# LOGIC.net
KiCad netlist of a schematic drawn in Altium Designer
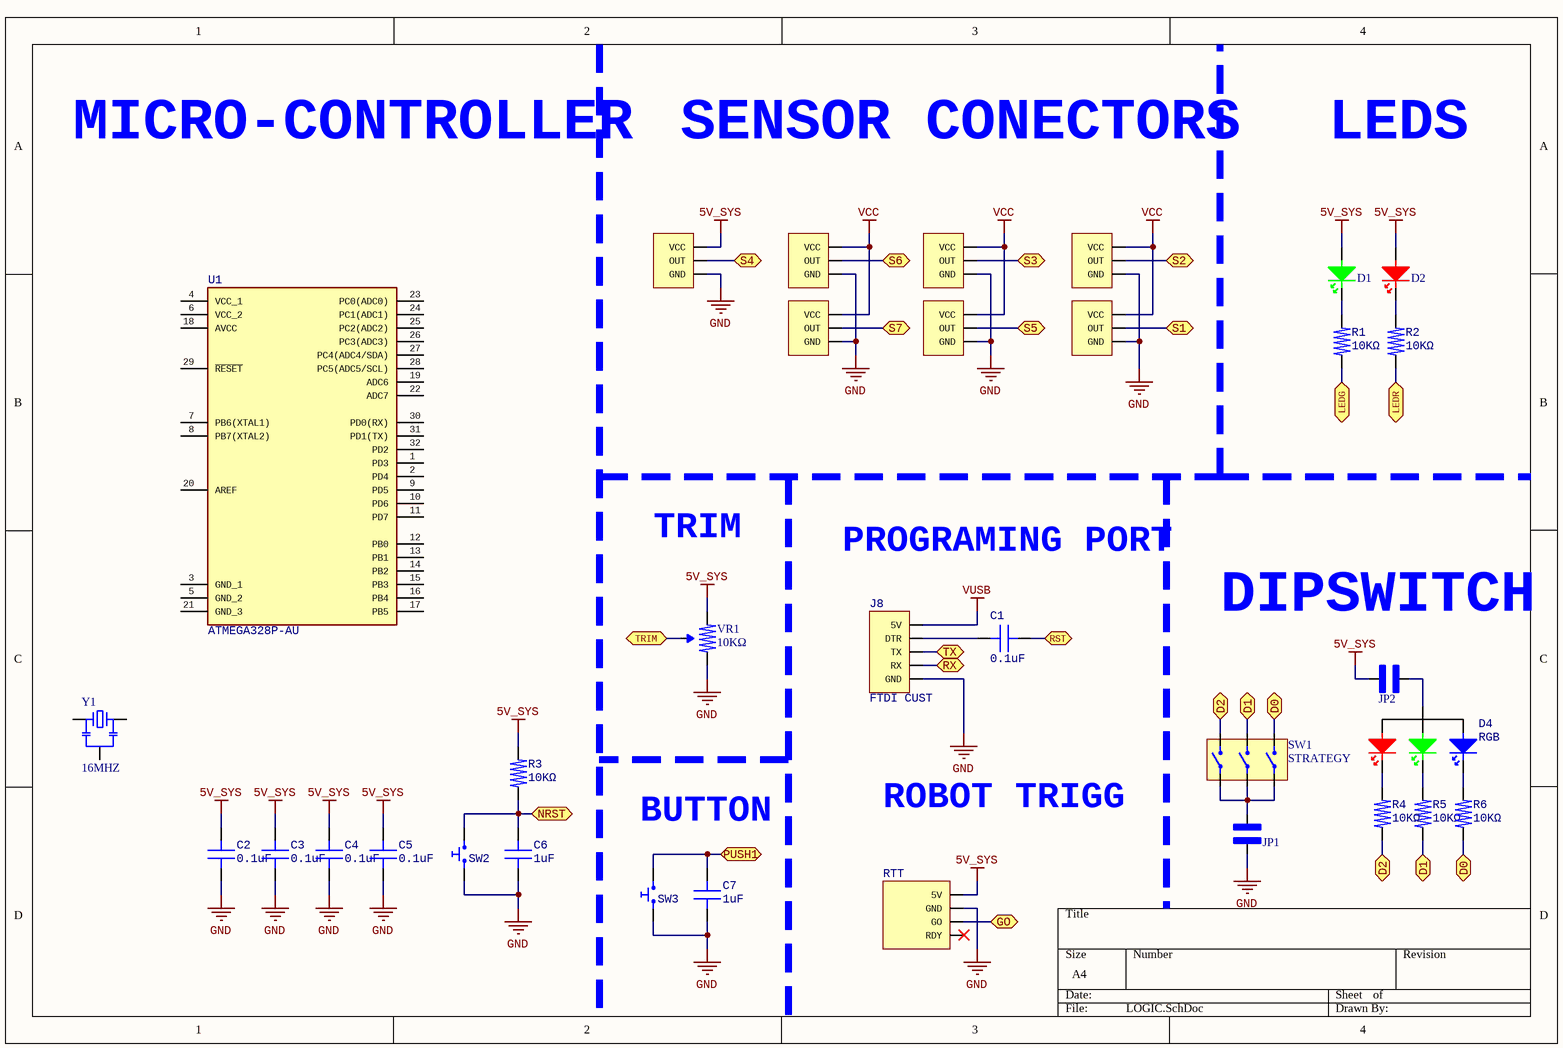
[diagram p0: LOGIC.SchDoc]

(export (version "E")
  (design (tool "Eeschema 10.0.6"))
  (components
    (comp (ref "C1")
      (value "0.1uF")
      (footprint "CAP0603")
      (description "Capacitor, Multilayer, Ceramic, 25V, 10%, X7R, 15% Tc, 0.1Uf, Surface Mount, 0603")
      (fields
        (field (name "MANUFACTURER") "KEMET")
        (field (name "MANUFACTURER PART NUMBER") "C0603C104K3RACTU")
      )
      (libsource (lib "CERAMIC CAPACITORS") (part "C0.1uF 25V X7R"))
    )
    (comp (ref "C2")
      (value "0.1uF")
      (footprint "CAP0603")
      (description "Capacitor, Multilayer, Ceramic, 25V, 10%, X7R, 15% Tc, 0.1Uf, Surface Mount, 0603")
      (fields
        (field (name "MANUFACTURER") "KEMET")
        (field (name "MANUFACTURER PART NUMBER") "C0603C104K3RACTU")
      )
      (libsource (lib "CERAMIC CAPACITORS") (part "C0.1uF 25V X7R"))
    )
    (comp (ref "C3")
      (value "0.1uF")
      (footprint "CAP0603")
      (description "Capacitor, Multilayer, Ceramic, 25V, 10%, X7R, 15% Tc, 0.1Uf, Surface Mount, 0603")
      (fields
        (field (name "MANUFACTURER") "KEMET")
        (field (name "MANUFACTURER PART NUMBER") "C0603C104K3RACTU")
      )
      (libsource (lib "CERAMIC CAPACITORS") (part "C0.1uF 25V X7R"))
    )
    (comp (ref "C4")
      (value "0.1uF")
      (footprint "CAP0603")
      (description "Capacitor, Multilayer, Ceramic, 25V, 10%, X7R, 15% Tc, 0.1Uf, Surface Mount, 0603")
      (fields
        (field (name "MANUFACTURER") "KEMET")
        (field (name "MANUFACTURER PART NUMBER") "C0603C104K3RACTU")
      )
      (libsource (lib "CERAMIC CAPACITORS") (part "C0.1uF 25V X7R"))
    )
    (comp (ref "C5")
      (value "0.1uF")
      (footprint "CAP0603")
      (description "Capacitor, Multilayer, Ceramic, 25V, 10%, X7R, 15% Tc, 0.1Uf, Surface Mount, 0603")
      (fields
        (field (name "MANUFACTURER") "KEMET")
        (field (name "MANUFACTURER PART NUMBER") "C0603C104K3RACTU")
      )
      (libsource (lib "CERAMIC CAPACITORS") (part "C0.1uF 25V X7R"))
    )
    (comp (ref "C6")
      (value "1uF")
      (footprint "CAP0603")
      (description "Multilayer Ceramic Capacitor, 1 uF, 50 V, ï¿½ 10%, X5R, 0603 [1608 Metric]")
      (fields
        (field (name "MANUFACTURER") "TDK")
        (field (name "MANUFACTURER PART NUMBER") "C1608X5R1H105K080AB")
      )
      (libsource (lib "CERAMIC CAPACITORS") (part "C1uF 50V X5R"))
    )
    (comp (ref "C7")
      (value "1uF")
      (footprint "CAP0603")
      (description "Multilayer Ceramic Capacitor, 1 uF, 50 V, ï¿½ 10%, X5R, 0603 [1608 Metric]")
      (fields
        (field (name "MANUFACTURER") "TDK")
        (field (name "MANUFACTURER PART NUMBER") "C1608X5R1H105K080AB")
      )
      (libsource (lib "CERAMIC CAPACITORS") (part "C1uF 50V X5R"))
    )
    (comp (ref "D1")
      (value "G")
      (footprint "LED0603 GREEN")
      (description "WURTH ELEKTRONIK - 150060VS75000 - LED, Green, SMD, 0603, 30 mA, 2 V, 570 nm")
      (fields
        (field (name "MANUFACTURER") "Wurth Electronics")
        (field (name "MANUFACTURER PART NUMBER") "150060VS75000")
      )
      (libsource (lib "LEDS") (part "GREEN LED 0603"))
    )
    (comp (ref "D2")
      (value "R")
      (footprint "LED0603 RED")
      (description "Led, Red, 630 Nm, 1.9 V, 30 Ma, 60 Mcd Rohs Compliant: Yes ¦Wurth Elektronik 150060SS75000")
      (fields
        (field (name "MANUFACTURER") "Wurth Electronics")
        (field (name "MANUFACTURER PART NUMBER") "150060SS75000")
      )
      (libsource (lib "LEDS") (part "RED LED 0603"))
    )
    (comp (ref "D4")
      (value "RGB")
      (footprint "LED RGB FM-B2020RGBA-HG")
      (description "LED RGB")
      (libsource (lib "LEDS") (part "RGB LED FM-B2020RGBA-HG"))
    )
    (comp (ref "J1")
      (value "GENERIC SENSOR 3X")
      (footprint "PINHEADER SENSOR CONNECTOR 3X")
      (description "PADS PARA CONECTAR UN SENSOR CON 1 LINEA DE VOLTAJE INDEPENDIENTE.")
      (libsource (lib "CONNECTORS") (part "GENERIC SENSOR 3X"))
    )
    (comp (ref "J2")
      (value "GENERIC SENSOR 3X")
      (footprint "PINHEADER SENSOR CONNECTOR 3X")
      (description "PADS PARA CONECTAR UN SENSOR CON 1 LINEA DE VOLTAJE INDEPENDIENTE.")
      (libsource (lib "CONNECTORS") (part "GENERIC SENSOR 3X"))
    )
    (comp (ref "J3")
      (value "GENERIC SENSOR 3X")
      (footprint "PINHEADER SENSOR CONNECTOR 3X")
      (description "PADS PARA CONECTAR UN SENSOR CON 1 LINEA DE VOLTAJE INDEPENDIENTE.")
      (libsource (lib "CONNECTORS") (part "GENERIC SENSOR 3X"))
    )
    (comp (ref "J4")
      (value "GENERIC SENSOR 3X")
      (footprint "PINHEADER SENSOR CONNECTOR 3X")
      (description "PADS PARA CONECTAR UN SENSOR CON 1 LINEA DE VOLTAJE INDEPENDIENTE.")
      (libsource (lib "CONNECTORS") (part "GENERIC SENSOR 3X"))
    )
    (comp (ref "J5")
      (value "GENERIC SENSOR 3X")
      (footprint "PINHEADER SENSOR CONNECTOR 3X")
      (description "PADS PARA CONECTAR UN SENSOR CON 1 LINEA DE VOLTAJE INDEPENDIENTE.")
      (libsource (lib "CONNECTORS") (part "GENERIC SENSOR 3X"))
    )
    (comp (ref "J6")
      (value "GENERIC SENSOR 3X")
      (footprint "PINHEADER SENSOR CONNECTOR 3X")
      (description "PADS PARA CONECTAR UN SENSOR CON 1 LINEA DE VOLTAJE INDEPENDIENTE.")
      (libsource (lib "CONNECTORS") (part "GENERIC SENSOR 3X"))
    )
    (comp (ref "J7")
      (value "GENERIC SENSOR 3X")
      (footprint "PINHEADER SENSOR CONNECTOR 3X")
      (description "PADS PARA CONECTAR UN SENSOR CON 1 LINEA DE VOLTAJE INDEPENDIENTE.")
      (libsource (lib "CONNECTORS") (part "GENERIC SENSOR 3X"))
    )
    (comp (ref "J8")
      (value "FTDI CUST")
      (footprint "UART PROG CONN")
      (description "GENERIC UART PROGRAMING PORT FOR ARDUINO CUSTOM BOARDS")
      (libsource (lib "CONNECTORS") (part "UART PROG"))
    )
    (comp (ref "J9")
      (value "RTT")
      (footprint "ING. MAKER RTT")
      (description "CONECTOR PINHEADER PARA ARRANCADPR ING. MAKER")
      (libsource (lib "CONNECTORS") (part "ING. MAKER RTT"))
    )
    (comp (ref "JP1")
      (value "ENABLE DPSW")
      (footprint "JUMPER 2 PADS")
      (description "JUMPER SMD CON 2 PADS NORMALMENTE ABIERTO")
      (libsource (lib "JUMPERS") (part "SINGLE JUMPER NO"))
    )
    (comp (ref "JP2")
      (value "ENABLE RGB")
      (footprint "JUMPER 2 PADS")
      (description "JUMPER SMD CON 2 PADS NORMALMENTE ABIERTO")
      (libsource (lib "JUMPERS") (part "SINGLE JUMPER NO"))
    )
    (comp (ref "R1")
      (value "10KΩ")
      (footprint "RES0603")
      (description "SMD Chip Resistor, 1 kOhm, ï¿½ 1%, 100 mW, 0603 [1608 Metric], Thick Film, General Purpose")
      (fields
        (field (name "MANUFACTURER") "Yageo")
        (field (name "MANUFACTURER PART NUMBER") "RC0603FR-101KL")
      )
      (libsource (lib "RESISTORS") (part "R1KΩ"))
    )
    (comp (ref "R2")
      (value "10KΩ")
      (footprint "RES0603")
      (description "SMD Chip Resistor, 1 kOhm, ï¿½ 1%, 100 mW, 0603 [1608 Metric], Thick Film, General Purpose")
      (fields
        (field (name "MANUFACTURER") "Yageo")
        (field (name "MANUFACTURER PART NUMBER") "RC0603FR-101KL")
      )
      (libsource (lib "RESISTORS") (part "R1KΩ"))
    )
    (comp (ref "R3")
      (value "10KΩ")
      (footprint "RES0603")
      (description "SMD Chip Resistor, 10 kOhm, ï¿½ 5%, 100 mW, 0603 [1608 Metric], Thick Film, General Purpose")
      (fields
        (field (name "MANUFACTURER") "Yageo")
        (field (name "MANUFACTURER PART NUMBER") "RC0603JR-0710KL")
      )
      (libsource (lib "RESISTORS") (part "R10KΩ"))
    )
    (comp (ref "R4")
      (value "10KΩ")
      (footprint "RES0603")
      (description "SMD Chip Resistor, 1 kOhm, ï¿½ 1%, 100 mW, 0603 [1608 Metric], Thick Film, General Purpose")
      (fields
        (field (name "MANUFACTURER") "Yageo")
        (field (name "MANUFACTURER PART NUMBER") "RC0603FR-101KL")
      )
      (libsource (lib "RESISTORS") (part "R1KΩ"))
    )
    (comp (ref "R5")
      (value "10KΩ")
      (footprint "RES0603")
      (description "SMD Chip Resistor, 1 kOhm, ï¿½ 1%, 100 mW, 0603 [1608 Metric], Thick Film, General Purpose")
      (fields
        (field (name "MANUFACTURER") "Yageo")
        (field (name "MANUFACTURER PART NUMBER") "RC0603FR-101KL")
      )
      (libsource (lib "RESISTORS") (part "R1KΩ"))
    )
    (comp (ref "R6")
      (value "10KΩ")
      (footprint "RES0603")
      (description "SMD Chip Resistor, 1 kOhm, ï¿½ 1%, 100 mW, 0603 [1608 Metric], Thick Film, General Purpose")
      (fields
        (field (name "MANUFACTURER") "Yageo")
        (field (name "MANUFACTURER PART NUMBER") "RC0603FR-101KL")
      )
      (libsource (lib "RESISTORS") (part "R1KΩ"))
    )
    (comp (ref "SW1")
      (value "STRATEGY")
      (footprint "2193MSTR")
      (description "Switch DIP ON OFF SPST 3 Raised Slide 0.1A 20VDC Gull Wing 2000Cycles 2.54mm SMD Tube")
      (fields (field (name "MANUFACTURER") "CTS") (field (name "MANUFACTURER PART NUMBER") "219-3MST"))
      (libsource (lib "DIP SWITCHES") (part "219-3MST"))
    )
    (comp (ref "SW2")
      (value "RESET")
      (footprint "PTS810SJK250SMTRLFS")
      (description "Switch Tactile N.O. SPST Button J-Bend 0.05A 16VDC 50000Cycle 2.55N SMD T/R")
      (fields
        (field (name "MANUFACTURER") "ITT C&K")
        (field (name "MANUFACTURER PART NUMBER") "PTS810SJK250SMTRLFS")
      )
      (libsource (lib "PUSH BUTTONS") (part "PTS810SJK250SMTR LFS"))
    )
    (comp (ref "SW3")
      (value "BUTTON1")
      (footprint "PTS810SJK250SMTRLFS")
      (description "Switch Tactile N.O. SPST Button J-Bend 0.05A 16VDC 50000Cycle 2.55N SMD T/R")
      (fields
        (field (name "MANUFACTURER") "ITT C&K")
        (field (name "MANUFACTURER PART NUMBER") "PTS810SJK250SMTRLFS")
      )
      (libsource (lib "PUSH BUTTONS") (part "PTS810SJK250SMTR LFS"))
    )
    (comp (ref "U1")
      (value "ATMEGA328P-AU")
      (footprint "TQFP-32")
      (description "Risc Microcontroller, 8-BIT, Flash, AVR Risc Cpu, 20MHZ, Cmos, PQFP32")
      (fields (field (name "MANUFACTURER") "Microchip"))
      (libsource (lib "MICRO CONTROLLERS") (part "ATMEGA328P-AU"))
    )
    (comp (ref "VR1")
      (value "10KΩ")
      (footprint "TC33X2503E")
      (description "Cermet trimmer potentiometer, 10 kΩ, 0.1 W, SMD, on top, TC33X-2-103E")
      (fields (field (name "MANUFACTURER") "Bourns") (field (name "MANUFACTURER PART NUMBER") "TC33X-2-103E"))
      (libsource (lib "VARIABLE RESISTORS") (part "10KΩ"))
    )
    (comp (ref "Y1")
      (value "16MHZ")
      (footprint "CSTCE16M0V53R0")
      (libsource (lib "CRYSTAL") (part "RESONATOR 16MHZ CSTCE16M0V53-R0"))
    )
  )
  (nets
    (net (code "1") (name "/D0") (class "Default")
      (node (ref "R6") (pin "1") (pinfunction "K_1") (pintype "passive"))
      (node (ref "SW1") (pin "4") (pinfunction "NO_2_4") (pintype "passive"))
    )
    (net (code "2") (name "/D1") (class "Default")
      (node (ref "R5") (pin "1") (pinfunction "K_1") (pintype "passive"))
      (node (ref "SW1") (pin "5") (pinfunction "NO_2_5") (pintype "passive"))
    )
    (net (code "3") (name "/D2") (class "Default")
      (node (ref "R4") (pin "1") (pinfunction "K_1") (pintype "passive"))
      (node (ref "SW1") (pin "6") (pinfunction "NO_2_6") (pintype "passive"))
    )
    (net (code "4") (name "/GO") (class "Default")
      (node (ref "J9") (pin "3") (pinfunction "GO_3") (pintype "passive"))
    )
    (net (code "5") (name "/LEDG") (class "Default")
      (node (ref "R1") (pin "1") (pinfunction "K_1") (pintype "passive"))
    )
    (net (code "6") (name "/LEDR") (class "Default")
      (node (ref "R2") (pin "1") (pinfunction "K_1") (pintype "passive"))
    )
    (net (code "7") (name "/NRST") (class "Default")
      (node (ref "C6") (pin "2") (pinfunction "A_2") (pintype "passive"))
      (node (ref "R3") (pin "1") (pinfunction "K_1") (pintype "passive"))
      (node (ref "SW2") (pin "2") (pinfunction "NO_2_2") (pintype "passive"))
    )
    (net (code "8") (name "/PUSH1") (class "Default")
      (node (ref "C7") (pin "2") (pinfunction "A_2") (pintype "passive"))
      (node (ref "SW3") (pin "2") (pinfunction "NO_2_2") (pintype "passive"))
    )
    (net (code "9") (name "/RST") (class "Default")
      (node (ref "C1") (pin "1") (pinfunction "K_1") (pintype "passive"))
    )
    (net (code "10") (name "/RX") (class "Default")
      (node (ref "J8") (pin "RX") (pinfunction "RX_RX") (pintype "passive"))
    )
    (net (code "11") (name "/S1") (class "Default")
      (node (ref "J4") (pin "3") (pinfunction "OUT_3") (pintype "passive"))
    )
    (net (code "12") (name "/S2") (class "Default")
      (node (ref "J3") (pin "3") (pinfunction "OUT_3") (pintype "passive"))
    )
    (net (code "13") (name "/S3") (class "Default")
      (node (ref "J7") (pin "3") (pinfunction "OUT_3") (pintype "passive"))
    )
    (net (code "14") (name "/S4") (class "Default")
      (node (ref "J1") (pin "3") (pinfunction "OUT_3") (pintype "passive"))
    )
    (net (code "15") (name "/S5") (class "Default")
      (node (ref "J5") (pin "3") (pinfunction "OUT_3") (pintype "passive"))
    )
    (net (code "16") (name "/S6") (class "Default")
      (node (ref "J2") (pin "3") (pinfunction "OUT_3") (pintype "passive"))
    )
    (net (code "17") (name "/S7") (class "Default")
      (node (ref "J6") (pin "3") (pinfunction "OUT_3") (pintype "passive"))
    )
    (net (code "18") (name "/TRIM") (class "Default")
      (node (ref "VR1") (pin "2") (pinfunction "WIPER_2") (pintype "passive"))
    )
    (net (code "19") (name "/TX") (class "Default")
      (node (ref "J8") (pin "TX") (pinfunction "TX_TX") (pintype "passive"))
    )
    (net (code "20") (name "5V_SYS") (class "Default")
      (node (ref "C2") (pin "2") (pinfunction "A_2") (pintype "passive"))
      (node (ref "C3") (pin "2") (pinfunction "A_2") (pintype "passive"))
      (node (ref "C4") (pin "2") (pinfunction "A_2") (pintype "passive"))
      (node (ref "C5") (pin "2") (pinfunction "A_2") (pintype "passive"))
      (node (ref "D1") (pin "2") (pinfunction "A_2") (pintype "passive"))
      (node (ref "D2") (pin "2") (pinfunction "A_2") (pintype "passive"))
      (node (ref "J1") (pin "2") (pinfunction "VCC_2") (pintype "passive"))
      (node (ref "J9") (pin "1") (pinfunction "5V_1") (pintype "passive"))
      (node (ref "JP2") (pin "C") (pinfunction "C_C") (pintype "passive"))
      (node (ref "R3") (pin "2") (pinfunction "A_2") (pintype "passive"))
      (node (ref "VR1") (pin "3") (pinfunction "CW_3") (pintype "passive"))
    )
    (net (code "21") (name "GND") (class "Default")
      (node (ref "C2") (pin "1") (pinfunction "K_1") (pintype "passive"))
      (node (ref "C3") (pin "1") (pinfunction "K_1") (pintype "passive"))
      (node (ref "C4") (pin "1") (pinfunction "K_1") (pintype "passive"))
      (node (ref "C5") (pin "1") (pinfunction "K_1") (pintype "passive"))
      (node (ref "C6") (pin "1") (pinfunction "K_1") (pintype "passive"))
      (node (ref "C7") (pin "1") (pinfunction "K_1") (pintype "passive"))
      (node (ref "J1") (pin "4") (pinfunction "GND_4") (pintype "passive"))
      (node (ref "J2") (pin "4") (pinfunction "GND_4") (pintype "passive"))
      (node (ref "J3") (pin "4") (pinfunction "GND_4") (pintype "passive"))
      (node (ref "J4") (pin "4") (pinfunction "GND_4") (pintype "passive"))
      (node (ref "J5") (pin "4") (pinfunction "GND_4") (pintype "passive"))
      (node (ref "J6") (pin "4") (pinfunction "GND_4") (pintype "passive"))
      (node (ref "J7") (pin "4") (pinfunction "GND_4") (pintype "passive"))
      (node (ref "J8") (pin "GND") (pinfunction "GND_GND") (pintype "passive"))
      (node (ref "J9") (pin "2") (pinfunction "GND_2") (pintype "passive"))
      (node (ref "JP1") (pin "C") (pinfunction "C_C") (pintype "passive"))
      (node (ref "SW2") (pin "1") (pinfunction "NO_1_1") (pintype "passive"))
      (node (ref "SW3") (pin "1") (pinfunction "NO_1_1") (pintype "passive"))
      (node (ref "VR1") (pin "1") (pinfunction "CCW_1") (pintype "passive"))
    )
    (net (code "22") (name "Net-(C1-A)") (class "Default")
      (node (ref "C1") (pin "2") (pinfunction "A_2") (pintype "passive"))
      (node (ref "J8") (pin "DTR") (pinfunction "DTR_DTR") (pintype "passive"))
    )
    (net (code "23") (name "Net-(D1-K)") (class "Default")
      (node (ref "D1") (pin "1") (pinfunction "K_1") (pintype "passive"))
      (node (ref "R1") (pin "2") (pinfunction "A_2") (pintype "passive"))
    )
    (net (code "24") (name "Net-(D2-K)") (class "Default")
      (node (ref "D2") (pin "1") (pinfunction "K_1") (pintype "passive"))
      (node (ref "R2") (pin "2") (pinfunction "A_2") (pintype "passive"))
    )
    (net (code "25") (name "Net-(D4-COM)") (class "Default")
      (node (ref "D4") (pin "3") (pinfunction "COM_3") (pintype "passive"))
      (node (ref "JP2") (pin "A") (pinfunction "A_A") (pintype "passive"))
    )
    (net (code "26") (name "Net-(JP1-PadA)") (class "Default")
      (node (ref "JP1") (pin "A") (pinfunction "A_A") (pintype "passive"))
      (node (ref "SW1") (pin "1") (pinfunction "NO_1_1") (pintype "passive"))
      (node (ref "SW1") (pin "2") (pinfunction "NO_1_2") (pintype "passive"))
      (node (ref "SW1") (pin "3") (pinfunction "NO_1_3") (pintype "passive"))
    )
    (net (code "27") (name "Net-(R4-A)") (class "Default")
      (node (ref "D4") (pin "1") (pinfunction "K_1") (pintype "passive"))
      (node (ref "R4") (pin "2") (pinfunction "A_2") (pintype "passive"))
    )
    (net (code "28") (name "Net-(R5-A)") (class "Default")
      (node (ref "D4") (pin "4") (pinfunction "K_4") (pintype "passive"))
      (node (ref "R5") (pin "2") (pinfunction "A_2") (pintype "passive"))
    )
    (net (code "29") (name "Net-(R6-A)") (class "Default")
      (node (ref "D4") (pin "2") (pinfunction "K_2") (pintype "passive"))
      (node (ref "R6") (pin "2") (pinfunction "A_2") (pintype "passive"))
    )
    (net (code "30") (name "VCC") (class "Default")
      (node (ref "J2") (pin "2") (pinfunction "VCC_2") (pintype "passive"))
      (node (ref "J3") (pin "2") (pinfunction "VCC_2") (pintype "passive"))
      (node (ref "J4") (pin "2") (pinfunction "VCC_2") (pintype "passive"))
      (node (ref "J5") (pin "2") (pinfunction "VCC_2") (pintype "passive"))
      (node (ref "J6") (pin "2") (pinfunction "VCC_2") (pintype "passive"))
      (node (ref "J7") (pin "2") (pinfunction "VCC_2") (pintype "passive"))
    )
    (net (code "31") (name "VUSB") (class "Default")
      (node (ref "J8") (pin "5V") (pinfunction "5V_5V") (pintype "passive"))
    )
    (net (code "32") (name "unconnected-(J9-RDY-Pad4)") (class "Default")
      (node (ref "J9") (pin "4") (pinfunction "RDY_4") (pintype "passive+no_connect"))
    )
    (net (code "33") (name "unconnected-(U1-ADC6-Pad19)") (class "Default")
      (node (ref "U1") (pin "19") (pinfunction "ADC6_19") (pintype "passive"))
    )
    (net (code "34") (name "unconnected-(U1-ADC7-Pad22)") (class "Default")
      (node (ref "U1") (pin "22") (pinfunction "ADC7_22") (pintype "passive"))
    )
    (net (code "35") (name "unconnected-(U1-AREF-Pad20)") (class "Default")
      (node (ref "U1") (pin "20") (pinfunction "AREF_20") (pintype "passive"))
    )
    (net (code "36") (name "unconnected-(U1-AVCC-Pad18)") (class "Default")
      (node (ref "U1") (pin "18") (pinfunction "AVCC_18") (pintype "passive"))
    )
    (net (code "37") (name "unconnected-(U1-GND_1-Pad3)") (class "Default")
      (node (ref "U1") (pin "3") (pinfunction "GND_1_3") (pintype "passive"))
    )
    (net (code "38") (name "unconnected-(U1-GND_2-Pad5)") (class "Default")
      (node (ref "U1") (pin "5") (pinfunction "GND_2_5") (pintype "passive"))
    )
    (net (code "39") (name "unconnected-(U1-GND_3-Pad21)") (class "Default")
      (node (ref "U1") (pin "21") (pinfunction "GND_3_21") (pintype "passive"))
    )
    (net (code "40") (name "unconnected-(U1-PB0-Pad12)") (class "Default")
      (node (ref "U1") (pin "12") (pinfunction "PB0_12") (pintype "passive"))
    )
    (net (code "41") (name "unconnected-(U1-PB1-Pad13)") (class "Default")
      (node (ref "U1") (pin "13") (pinfunction "PB1_13") (pintype "passive"))
    )
    (net (code "42") (name "unconnected-(U1-PB2-Pad14)") (class "Default")
      (node (ref "U1") (pin "14") (pinfunction "PB2_14") (pintype "passive"))
    )
    (net (code "43") (name "unconnected-(U1-PB3-Pad15)") (class "Default")
      (node (ref "U1") (pin "15") (pinfunction "PB3_15") (pintype "passive"))
    )
    (net (code "44") (name "unconnected-(U1-PB4-Pad16)") (class "Default")
      (node (ref "U1") (pin "16") (pinfunction "PB4_16") (pintype "passive"))
    )
    (net (code "45") (name "unconnected-(U1-PB5-Pad17)") (class "Default")
      (node (ref "U1") (pin "17") (pinfunction "PB5_17") (pintype "passive"))
    )
    (net (code "46") (name "unconnected-(U1-PB6(XTAL1)-Pad7)") (class "Default")
      (node (ref "U1") (pin "7") (pinfunction "PB6(XTAL1)_7") (pintype "passive"))
    )
    (net (code "47") (name "unconnected-(U1-PB7(XTAL2)-Pad8)") (class "Default")
      (node (ref "U1") (pin "8") (pinfunction "PB7(XTAL2)_8") (pintype "passive"))
    )
    (net (code "48") (name "unconnected-(U1-PC0(ADC0)-Pad23)") (class "Default")
      (node (ref "U1") (pin "23") (pinfunction "PC0(ADC0)_23") (pintype "passive"))
    )
    (net (code "49") (name "unconnected-(U1-PC1(ADC1)-Pad24)") (class "Default")
      (node (ref "U1") (pin "24") (pinfunction "PC1(ADC1)_24") (pintype "passive"))
    )
    (net (code "50") (name "unconnected-(U1-PC2(ADC2)-Pad25)") (class "Default")
      (node (ref "U1") (pin "25") (pinfunction "PC2(ADC2)_25") (pintype "passive"))
    )
    (net (code "51") (name "unconnected-(U1-PC3(ADC3)-Pad26)") (class "Default")
      (node (ref "U1") (pin "26") (pinfunction "PC3(ADC3)_26") (pintype "passive"))
    )
    (net (code "52") (name "unconnected-(U1-PC4(ADC4{slash}SDA)-Pad27)") (class "Default")
      (node (ref "U1") (pin "27") (pinfunction "PC4(ADC4/SDA)_27") (pintype "passive"))
    )
    (net (code "53") (name "unconnected-(U1-PC5(ADC5{slash}SCL)-Pad28)") (class "Default")
      (node (ref "U1") (pin "28") (pinfunction "PC5(ADC5/SCL)_28") (pintype "passive"))
    )
    (net (code "54") (name "unconnected-(U1-PD0(RX)-Pad30)") (class "Default")
      (node (ref "U1") (pin "30") (pinfunction "PD0(RX)_30") (pintype "passive"))
    )
    (net (code "55") (name "unconnected-(U1-PD1(TX)-Pad31)") (class "Default")
      (node (ref "U1") (pin "31") (pinfunction "PD1(TX)_31") (pintype "passive"))
    )
    (net (code "56") (name "unconnected-(U1-PD2-Pad32)") (class "Default")
      (node (ref "U1") (pin "32") (pinfunction "PD2_32") (pintype "passive"))
    )
    (net (code "57") (name "unconnected-(U1-PD3-Pad1)") (class "Default")
      (node (ref "U1") (pin "1") (pinfunction "PD3_1") (pintype "passive"))
    )
    (net (code "58") (name "unconnected-(U1-PD4-Pad2)") (class "Default")
      (node (ref "U1") (pin "2") (pinfunction "PD4_2") (pintype "passive"))
    )
    (net (code "59") (name "unconnected-(U1-PD5-Pad9)") (class "Default")
      (node (ref "U1") (pin "9") (pinfunction "PD5_9") (pintype "passive"))
    )
    (net (code "60") (name "unconnected-(U1-PD6-Pad10)") (class "Default")
      (node (ref "U1") (pin "10") (pinfunction "PD6_10") (pintype "passive"))
    )
    (net (code "61") (name "unconnected-(U1-PD7-Pad11)") (class "Default")
      (node (ref "U1") (pin "11") (pinfunction "PD7_11") (pintype "passive"))
    )
    (net (code "62") (name "unconnected-(U1-VCC_1-Pad4)") (class "Default")
      (node (ref "U1") (pin "4") (pinfunction "VCC_1_4") (pintype "passive"))
    )
    (net (code "63") (name "unconnected-(U1-VCC_2-Pad6)") (class "Default")
      (node (ref "U1") (pin "6") (pinfunction "VCC_2_6") (pintype "passive"))
    )
    (net (code "64") (name "unconnected-(U1-~{RESET}-Pad29)") (class "Default")
      (node (ref "U1") (pin "29") (pinfunction "~{RESET}_29") (pintype "passive"))
    )
    (net (code "65") (name "unconnected-(Y1-Pad1)") (class "Default")
      (node (ref "Y1") (pin "1") (pinfunction "1_1") (pintype "passive"))
    )
    (net (code "66") (name "unconnected-(Y1-Pad3)") (class "Default")
      (node (ref "Y1") (pin "3") (pinfunction "3_3") (pintype "passive"))
    )
    (net (code "67") (name "unconnected-(Y1-Pad4)") (class "Default")
      (node (ref "Y1") (pin "4") (pinfunction "4_4") (pintype "passive"))
    )
  )
)
